# USB.net
KiCad netlist of a schematic drawn in Altium Designer
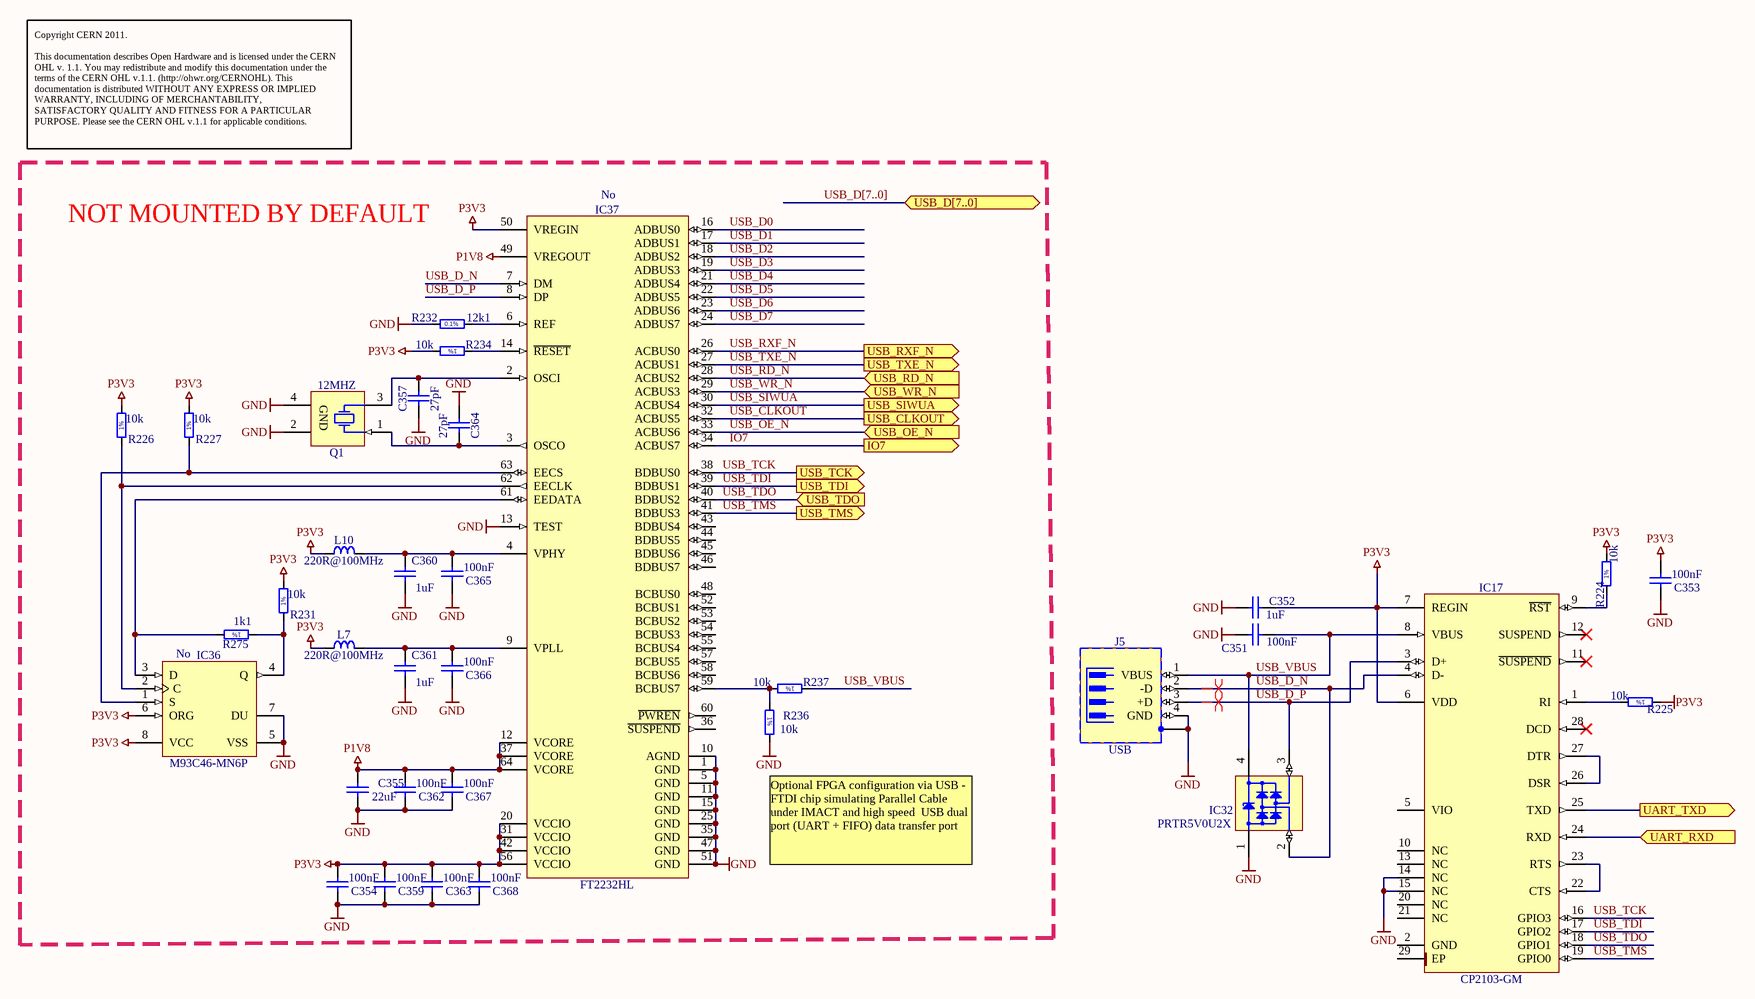
[diagram p0: USB.SchDoc]

(export (version "E")
  (design (tool "Eeschema 10.0.6"))
  (components
    (comp (ref "C351")
      (value "100nF")
      (footprint "CAPC1005X55N")
      (description "Non-polarised capacitor")
      (fields
        (field (name "PART NUMBER") "CC0402_100NF_16V_10%_X7R")
        (field (name "VOLTAGE") "16V")
        (field (name "AUTHOR") "CERN DEM JLC")
      )
      (libsource (lib "Capacitors") (part "Capacitor - non polarized"))
    )
    (comp (ref "C352")
      (value "1uF")
      (footprint "CAPC1608X87N")
      (description "Non-polarised capacitor")
      (fields
        (field (name "PART NUMBER") "CC0603_1UF_16V_10%_X7R")
        (field (name "VOLTAGE") "16V")
        (field (name "AUTHOR") "CERN DEM JLC")
      )
      (libsource (lib "Capacitors") (part "Capacitor - non polarized"))
    )
    (comp (ref "C353")
      (value "100nF")
      (footprint "CAPC1005X55N")
      (description "Non-polarised capacitor")
      (fields
        (field (name "PART NUMBER") "CC0402_100NF_16V_10%_X7R")
        (field (name "VOLTAGE") "16V")
        (field (name "AUTHOR") "CERN DEM JLC")
      )
      (libsource (lib "Capacitors") (part "Capacitor - non polarized"))
    )
    (comp (ref "C354")
      (value "100nF")
      (footprint "CAPC1005X55N")
      (description "Non-polarised capacitor")
      (fields
        (field (name "PART NUMBER") "CC0402_100NF_16V_10%_X7R")
        (field (name "VOLTAGE") "16V")
        (field (name "AUTHOR") "CERN DEM JLC")
      )
      (libsource (lib "Capacitors") (part "Capacitor - non polarized"))
    )
    (comp (ref "C355")
      (value "22uF")
      (footprint "CAPC3216X180N")
      (description "Non-polarised capacitor")
      (fields
        (field (name "PART NUMBER") "CC1206_22UF_10V_10%_X7R")
        (field (name "VOLTAGE") "10V")
        (field (name "AUTHOR") "CERN DEM JLC")
      )
      (libsource (lib "Capacitors") (part "Capacitor - non polarized"))
    )
    (comp (ref "C357")
      (value "27pF")
      (footprint "CAPC1608X87N")
      (description "Non-polarised capacitor")
      (fields
        (field (name "PART NUMBER") "CC0603_27PF_50V_5%_NP0")
        (field (name "VOLTAGE") "50V")
        (field (name "AUTHOR") "CERN DEM JLC")
      )
      (libsource (lib "Capacitors") (part "Capacitor - non polarized"))
    )
    (comp (ref "C359")
      (value "100nF")
      (footprint "CAPC1005X55N")
      (description "Non-polarised capacitor")
      (fields
        (field (name "PART NUMBER") "CC0402_100NF_16V_10%_X7R")
        (field (name "VOLTAGE") "16V")
        (field (name "AUTHOR") "CERN DEM JLC")
      )
      (libsource (lib "Capacitors") (part "Capacitor - non polarized"))
    )
    (comp (ref "C360")
      (value "1uF")
      (footprint "CAPC1608X87N")
      (description "Non-polarised capacitor")
      (fields
        (field (name "PART NUMBER") "CC0603_1UF_16V_10%_X7R")
        (field (name "VOLTAGE") "16V")
        (field (name "AUTHOR") "CERN DEM JLC")
      )
      (libsource (lib "Capacitors") (part "Capacitor - non polarized"))
    )
    (comp (ref "C361")
      (value "1uF")
      (footprint "CAPC1608X87N")
      (description "Non-polarised capacitor")
      (fields
        (field (name "PART NUMBER") "CC0603_1UF_16V_10%_X7R")
        (field (name "VOLTAGE") "16V")
        (field (name "AUTHOR") "CERN DEM JLC")
      )
      (libsource (lib "Capacitors") (part "Capacitor - non polarized"))
    )
    (comp (ref "C362")
      (value "100nF")
      (footprint "CAPC1005X55N")
      (description "Non-polarised capacitor")
      (fields
        (field (name "PART NUMBER") "CC0402_100NF_16V_10%_X7R")
        (field (name "VOLTAGE") "16V")
        (field (name "AUTHOR") "CERN DEM JLC")
      )
      (libsource (lib "Capacitors") (part "Capacitor - non polarized"))
    )
    (comp (ref "C363")
      (value "100nF")
      (footprint "CAPC1005X55N")
      (description "Non-polarised capacitor")
      (fields
        (field (name "PART NUMBER") "CC0402_100NF_16V_10%_X7R")
        (field (name "VOLTAGE") "16V")
        (field (name "AUTHOR") "CERN DEM JLC")
      )
      (libsource (lib "Capacitors") (part "Capacitor - non polarized"))
    )
    (comp (ref "C364")
      (value "27pF")
      (footprint "CAPC1608X87N")
      (description "Non-polarised capacitor")
      (fields
        (field (name "PART NUMBER") "CC0603_27PF_50V_5%_NP0")
        (field (name "VOLTAGE") "50V")
        (field (name "AUTHOR") "CERN DEM JLC")
      )
      (libsource (lib "Capacitors") (part "Capacitor - non polarized"))
    )
    (comp (ref "C365")
      (value "100nF")
      (footprint "CAPC1005X55N")
      (description "Non-polarised capacitor")
      (fields
        (field (name "PART NUMBER") "CC0402_100NF_16V_10%_X7R")
        (field (name "VOLTAGE") "16V")
        (field (name "AUTHOR") "CERN DEM JLC")
      )
      (libsource (lib "Capacitors") (part "Capacitor - non polarized"))
    )
    (comp (ref "C366")
      (value "100nF")
      (footprint "CAPC1005X55N")
      (description "Non-polarised capacitor")
      (fields
        (field (name "PART NUMBER") "CC0402_100NF_16V_10%_X7R")
        (field (name "VOLTAGE") "16V")
        (field (name "AUTHOR") "CERN DEM JLC")
      )
      (libsource (lib "Capacitors") (part "Capacitor - non polarized"))
    )
    (comp (ref "C367")
      (value "100nF")
      (footprint "CAPC1005X55N")
      (description "Non-polarised capacitor")
      (fields
        (field (name "PART NUMBER") "CC0402_100NF_16V_10%_X7R")
        (field (name "VOLTAGE") "16V")
        (field (name "AUTHOR") "CERN DEM JLC")
      )
      (libsource (lib "Capacitors") (part "Capacitor - non polarized"))
    )
    (comp (ref "C368")
      (value "100nF")
      (footprint "CAPC1005X55N")
      (description "Non-polarised capacitor")
      (fields
        (field (name "PART NUMBER") "CC0402_100NF_16V_10%_X7R")
        (field (name "VOLTAGE") "16V")
        (field (name "AUTHOR") "CERN DEM JLC")
      )
      (libsource (lib "Capacitors") (part "Capacitor - non polarized"))
    )
    (comp (ref "IC17")
      (value "CP2103-GM")
      (footprint "QFN50P500X500X100-29N-S335")
      (description "Single-Chip USB to UART Bridge")
      (fields (field (name "MANUFACTURER") "SILICON LABS") (field (name "AUTHOR") "CERN DEM JLC"))
      (libsource (lib "ICs And Semiconductors") (part "CP2103-GM"))
    )
    (comp (ref "IC32")
      (value "PRTR5V0U2X")
      (footprint "SOT190P230X110-4N")
      (description "Ultra Low Capacitance Double Rail-to-Rail ESD Protection Diode")
      (fields
        (field (name "VOLTAGE") "5.5V")
        (field (name "MANUFACTURER") "PHILIPS NXP")
        (field (name "AUTHOR") "CERN DEM JLC")
      )
      (libsource (lib "ICs And Semiconductors") (part "PRTR5V0U2X"))
    )
    (comp (ref "IC36")
      (value "M93C46-MN6P")
      (footprint "SOIC127P600X175-8N")
      (description "1Kb (x8/x16) Serial Microwire Bus EEPROM")
      (fields
        (field (name "MANUFACTURER") "ST MICROELECTRONICS")
        (field (name "MOUNTED") "No")
        (field (name "AUTHOR") "CERN DEM JLC")
      )
      (libsource (lib "ICs And Semiconductors") (part "M93C46-MN"))
    )
    (comp (ref "IC37")
      (value "FT2232HL")
      (footprint "QFP50P1200X1200X160-64N")
      (description "Dual High Speed USB to Multipurpose UART/FIFO IC")
      (fields
        (field (name "MANUFACTURER") "FUTURE TECHNOLOGY DEVICES INTERNATIONAL (FTDI)")
        (field (name "MOUNTED") "No")
        (field (name "AUTHOR") "CERN DEM JLC")
      )
      (libsource (lib "ICs And Semiconductors") (part "FT2232H"))
    )
    (comp (ref "J5")
      (value "USB")
      (footprint "TYCO_292304-1")
      (description "4 Pin + 1 Shield USB Receptacle")
      (fields
        (field (name "PART NUMBER") "TYCO_292304-1")
        (field (name "MANUFACTURER") "TYCO ELECTRONICS")
        (field (name "AUTHOR") "CERN DEM JLC")
      )
      (libsource (lib "Connectors") (part "Connector USB 4 Pin + 1Shield"))
    )
    (comp (ref "L7")
      (value "220R@100MHz")
      (footprint "INDC2012X105N")
      (description "Inductor")
      (fields
        (field (name "PART NUMBER") "IND0805_MURATA_BLM21PG221SN1D")
        (field (name "POWER") "2A")
        (field (name "AUTHOR") "CERN DEM JLC")
      )
      (libsource (lib "Inductors & Transformers") (part "Inductor"))
    )
    (comp (ref "L10")
      (value "220R@100MHz")
      (footprint "INDC2012X105N")
      (description "Inductor")
      (fields
        (field (name "PART NUMBER") "IND0805_MURATA_BLM21PG221SN1D")
        (field (name "POWER") "2A")
        (field (name "AUTHOR") "CERN DEM JLC")
      )
      (libsource (lib "Inductors & Transformers") (part "Inductor"))
    )
    (comp (ref "Q1")
      (value "12MHZ")
      (footprint "XTAL_ABRACON_ABM3B")
      (description "Crystal 4 pins 1=XTAL Control 2=GND3=XTAL 4=GND")
      (fields
        (field (name "PART NUMBER") "XTAL_12MHZ_ABRACON_ABM3B-12.000MHZ-B2-T")
        (field (name "MANUFACTURER") "ABRACON")
        (field (name "AUTHOR") "CERN DEM JLC")
      )
      (libsource (lib "ICs And Semiconductors") (part "Quartz Crystal 1X 2GND 3X 4GND"))
    )
    (comp (ref "R224")
      (value "10k")
      (footprint "RESC1608X55N")
      (description "Resistor - 1%")
      (fields
        (field (name "PART NUMBER") "R0603_10K_1%_0.1W_100PPM")
        (field (name "POWER") "0.1W")
        (field (name "AUTHOR") "CERN DEM JLC")
      )
      (libsource (lib "Resistors") (part "Resistor - 1%"))
    )
    (comp (ref "R225")
      (value "10k")
      (footprint "RESC1608X55N")
      (description "Resistor - 1%")
      (fields
        (field (name "PART NUMBER") "R0603_10K_1%_0.1W_100PPM")
        (field (name "POWER") "0.1W")
        (field (name "AUTHOR") "CERN DEM JLC")
      )
      (libsource (lib "Resistors") (part "Resistor - 1%"))
    )
    (comp (ref "R226")
      (value "10k")
      (footprint "RESC1608X55N")
      (description "Resistor - 1%")
      (fields
        (field (name "PART NUMBER") "R0603_10K_1%_0.1W_100PPM")
        (field (name "POWER") "0.1W")
        (field (name "AUTHOR") "CERN DEM JLC")
      )
      (libsource (lib "Resistors") (part "Resistor - 1%"))
    )
    (comp (ref "R227")
      (value "10k")
      (footprint "RESC1608X55N")
      (description "Resistor - 1%")
      (fields
        (field (name "PART NUMBER") "R0603_10K_1%_0.1W_100PPM")
        (field (name "POWER") "0.1W")
        (field (name "AUTHOR") "CERN DEM JLC")
      )
      (libsource (lib "Resistors") (part "Resistor - 1%"))
    )
    (comp (ref "R231")
      (value "10k")
      (footprint "RESC1608X55N")
      (description "Resistor - 1%")
      (fields
        (field (name "PART NUMBER") "R0603_10K_1%_0.1W_100PPM")
        (field (name "POWER") "0.1W")
        (field (name "AUTHOR") "CERN DEM JLC")
      )
      (libsource (lib "Resistors") (part "Resistor - 1%"))
    )
    (comp (ref "R232")
      (value "12k1")
      (footprint "RESC1608X55N")
      (description "Resistor - 0.1%")
      (fields
        (field (name "PART NUMBER") "R0603_12K1_0.1%_0.063W_10PPM")
        (field (name "POWER") "0.063W")
        (field (name "AUTHOR") "CERN DEM JLC")
      )
      (libsource (lib "Resistors") (part "Resistor - 0.1%"))
    )
    (comp (ref "R234")
      (value "10k")
      (footprint "RESC1608X55N")
      (description "Resistor - 1%")
      (fields
        (field (name "PART NUMBER") "R0603_10K_1%_0.1W_100PPM")
        (field (name "POWER") "0.1W")
        (field (name "AUTHOR") "CERN DEM JLC")
      )
      (libsource (lib "Resistors") (part "Resistor - 1%"))
    )
    (comp (ref "R236")
      (value "10k")
      (footprint "RESC1608X55N")
      (description "Resistor - 1%")
      (fields
        (field (name "PART NUMBER") "R0603_10K_1%_0.1W_100PPM")
        (field (name "POWER") "0.1W")
        (field (name "AUTHOR") "CERN DEM JLC")
      )
      (libsource (lib "Resistors") (part "Resistor - 1%"))
    )
    (comp (ref "R237")
      (value "10k")
      (footprint "RESC1608X55N")
      (description "Resistor - 1%")
      (fields
        (field (name "PART NUMBER") "R0603_10K_1%_0.1W_100PPM")
        (field (name "POWER") "0.1W")
        (field (name "AUTHOR") "CERN DEM JLC")
      )
      (libsource (lib "Resistors") (part "Resistor - 1%"))
    )
    (comp (ref "R275")
      (value "1k1")
      (footprint "RESC1608X55N")
      (description "Resistor - 1%")
      (fields
        (field (name "PART NUMBER") "R0603_1K1_1%_0.1W_100PPM")
        (field (name "POWER") "0.1W")
        (field (name "AUTHOR") "CERN DEM JLC")
      )
      (libsource (lib "Resistors") (part "Resistor - 1%"))
    )
  )
  (nets
    (net (code "1") (name "/IO7") (class "Default")
      (node (ref "IC37") (pin "34") (pinfunction "ACBUS7_34") (pintype "bidirectional"))
    )
    (net (code "2") (name "/UART_RXD") (class "Default")
      (node (ref "IC17") (pin "24") (pinfunction "RXD_24") (pintype "input"))
    )
    (net (code "3") (name "/UART_TXD") (class "Default")
      (node (ref "IC17") (pin "25") (pinfunction "TXD_25") (pintype "output"))
    )
    (net (code "4") (name "/USB_CLKOUT") (class "Default")
      (node (ref "IC37") (pin "32") (pinfunction "ACBUS5_32") (pintype "bidirectional"))
    )
    (net (code "5") (name "/USB_D0") (class "Default")
      (node (ref "IC37") (pin "16") (pinfunction "ADBUS0_16") (pintype "bidirectional"))
    )
    (net (code "6") (name "/USB_D1") (class "Default")
      (node (ref "IC37") (pin "17") (pinfunction "ADBUS1_17") (pintype "bidirectional"))
    )
    (net (code "7") (name "/USB_D2") (class "Default")
      (node (ref "IC37") (pin "18") (pinfunction "ADBUS2_18") (pintype "bidirectional"))
    )
    (net (code "8") (name "/USB_D3") (class "Default")
      (node (ref "IC37") (pin "19") (pinfunction "ADBUS3_19") (pintype "bidirectional"))
    )
    (net (code "9") (name "/USB_D4") (class "Default")
      (node (ref "IC37") (pin "21") (pinfunction "ADBUS4_21") (pintype "bidirectional"))
    )
    (net (code "10") (name "/USB_D5") (class "Default")
      (node (ref "IC37") (pin "22") (pinfunction "ADBUS5_22") (pintype "bidirectional"))
    )
    (net (code "11") (name "/USB_D6") (class "Default")
      (node (ref "IC37") (pin "23") (pinfunction "ADBUS6_23") (pintype "bidirectional"))
    )
    (net (code "12") (name "/USB_D7") (class "Default")
      (node (ref "IC37") (pin "24") (pinfunction "ADBUS7_24") (pintype "bidirectional"))
    )
    (net (code "14") (name "/USB_D_N") (class "Default")
      (node (ref "IC17") (pin "4") (pinfunction "D-_4") (pintype "bidirectional"))
      (node (ref "IC32") (pin "2") (pinfunction "I/O1_2") (pintype "bidirectional"))
      (node (ref "IC37") (pin "7") (pinfunction "DM_7") (pintype "input"))
      (node (ref "J5") (pin "2") (pinfunction "-D_2") (pintype "bidirectional"))
    )
    (net (code "15") (name "/USB_D_P") (class "Default")
      (node (ref "IC17") (pin "3") (pinfunction "D+_3") (pintype "bidirectional"))
      (node (ref "IC32") (pin "3") (pinfunction "I/O2_3") (pintype "bidirectional"))
      (node (ref "IC37") (pin "8") (pinfunction "DP_8") (pintype "input"))
      (node (ref "J5") (pin "3") (pinfunction "+D_3") (pintype "bidirectional"))
    )
    (net (code "16") (name "/USB_OE_N") (class "Default")
      (node (ref "IC37") (pin "33") (pinfunction "ACBUS6_33") (pintype "bidirectional"))
    )
    (net (code "17") (name "/USB_RD_N") (class "Default")
      (node (ref "IC37") (pin "28") (pinfunction "ACBUS2_28") (pintype "bidirectional"))
    )
    (net (code "18") (name "/USB_RXF_N") (class "Default")
      (node (ref "IC37") (pin "26") (pinfunction "ACBUS0_26") (pintype "bidirectional"))
    )
    (net (code "19") (name "/USB_SIWUA") (class "Default")
      (node (ref "IC37") (pin "30") (pinfunction "ACBUS4_30") (pintype "bidirectional"))
    )
    (net (code "20") (name "/USB_TCK") (class "Default")
      (node (ref "IC17") (pin "16") (pinfunction "GPIO3_16") (pintype "bidirectional"))
      (node (ref "IC37") (pin "38") (pinfunction "BDBUS0_38") (pintype "bidirectional"))
    )
    (net (code "21") (name "/USB_TDI") (class "Default")
      (node (ref "IC17") (pin "17") (pinfunction "GPIO2_17") (pintype "bidirectional"))
      (node (ref "IC37") (pin "39") (pinfunction "BDBUS1_39") (pintype "bidirectional"))
    )
    (net (code "22") (name "/USB_TDO") (class "Default")
      (node (ref "IC17") (pin "18") (pinfunction "GPIO1_18") (pintype "bidirectional"))
      (node (ref "IC37") (pin "40") (pinfunction "BDBUS2_40") (pintype "bidirectional"))
    )
    (net (code "23") (name "/USB_TMS") (class "Default")
      (node (ref "IC17") (pin "19") (pinfunction "GPIO0_19") (pintype "bidirectional"))
      (node (ref "IC37") (pin "41") (pinfunction "BDBUS3_41") (pintype "bidirectional"))
    )
    (net (code "24") (name "/USB_TXE_N") (class "Default")
      (node (ref "IC37") (pin "27") (pinfunction "ACBUS1_27") (pintype "bidirectional"))
    )
    (net (code "25") (name "/USB_VBUS") (class "Default")
      (node (ref "C351") (pin "1") (pinfunction "1_1") (pintype "passive"))
      (node (ref "IC17") (pin "8") (pinfunction "VBUS_8") (pintype "input"))
      (node (ref "IC32") (pin "4") (pinfunction "VCC_4") (pintype "power_in"))
      (node (ref "J5") (pin "1") (pinfunction "VBUS_1") (pintype "bidirectional"))
      (node (ref "R237") (pin "1") (pinfunction "1_1") (pintype "passive"))
    )
    (net (code "26") (name "/USB_WR_N") (class "Default")
      (node (ref "IC37") (pin "29") (pinfunction "ACBUS3_29") (pintype "bidirectional"))
    )
    (net (code "27") (name "GND") (class "Default")
      (node (ref "C351") (pin "2") (pinfunction "2_2") (pintype "passive"))
      (node (ref "C352") (pin "2") (pinfunction "2_2") (pintype "passive"))
      (node (ref "C353") (pin "2") (pinfunction "2_2") (pintype "passive"))
      (node (ref "C354") (pin "2") (pinfunction "2_2") (pintype "passive"))
      (node (ref "C355") (pin "1") (pinfunction "1_1") (pintype "passive"))
      (node (ref "C357") (pin "1") (pinfunction "1_1") (pintype "passive"))
      (node (ref "C359") (pin "2") (pinfunction "2_2") (pintype "passive"))
      (node (ref "C360") (pin "1") (pinfunction "1_1") (pintype "passive"))
      (node (ref "C361") (pin "1") (pinfunction "1_1") (pintype "passive"))
      (node (ref "C362") (pin "2") (pinfunction "2_2") (pintype "passive"))
      (node (ref "C363") (pin "2") (pinfunction "2_2") (pintype "passive"))
      (node (ref "C364") (pin "1") (pinfunction "1_1") (pintype "passive"))
      (node (ref "C365") (pin "2") (pinfunction "2_2") (pintype "passive"))
      (node (ref "C366") (pin "2") (pinfunction "2_2") (pintype "passive"))
      (node (ref "C367") (pin "2") (pinfunction "2_2") (pintype "passive"))
      (node (ref "C368") (pin "2") (pinfunction "2_2") (pintype "passive"))
      (node (ref "IC17") (pin "14") (pinfunction "NC_14") (pintype "passive"))
      (node (ref "IC17") (pin "15") (pinfunction "NC_15") (pintype "passive"))
      (node (ref "IC32") (pin "1") (pinfunction "GND_1") (pintype "power_in"))
      (node (ref "IC36") (pin "5") (pinfunction "VSS_5") (pintype "power_in"))
      (node (ref "IC36") (pin "7") (pinfunction "DU_7") (pintype "passive"))
      (node (ref "IC37") (pin "1") (pinfunction "GND_1") (pintype "power_in"))
      (node (ref "IC37") (pin "10") (pinfunction "AGND_10") (pintype "power_in"))
      (node (ref "IC37") (pin "11") (pinfunction "GND_11") (pintype "power_in"))
      (node (ref "IC37") (pin "13") (pinfunction "TEST_13") (pintype "input"))
      (node (ref "IC37") (pin "15") (pinfunction "GND_15") (pintype "power_in"))
      (node (ref "IC37") (pin "25") (pinfunction "GND_25") (pintype "power_in"))
      (node (ref "IC37") (pin "35") (pinfunction "GND_35") (pintype "power_in"))
      (node (ref "IC37") (pin "47") (pinfunction "GND_47") (pintype "power_in"))
      (node (ref "IC37") (pin "5") (pinfunction "GND_5") (pintype "power_in"))
      (node (ref "IC37") (pin "51") (pinfunction "GND_51") (pintype "power_in"))
      (node (ref "J5") (pin "4") (pinfunction "GND_4") (pintype "bidirectional"))
      (node (ref "J5") (pin "5") (pinfunction "SH_5") (pintype "power_in"))
      (node (ref "Q1") (pin "2") (pinfunction "GND_2") (pintype "power_in"))
      (node (ref "Q1") (pin "4") (pinfunction "GND_4") (pintype "power_in"))
      (node (ref "R232") (pin "1") (pinfunction "1_1") (pintype "passive"))
      (node (ref "R236") (pin "2") (pinfunction "2_2") (pintype "passive"))
    )
    (net (code "28") (name "Net-(IC17-CTS)") (class "Default")
      (node (ref "IC17") (pin "22") (pinfunction "CTS_22") (pintype "input"))
      (node (ref "IC17") (pin "23") (pinfunction "RTS_23") (pintype "output"))
    )
    (net (code "29") (name "Net-(IC17-DSR)") (class "Default")
      (node (ref "IC17") (pin "26") (pinfunction "DSR_26") (pintype "input"))
      (node (ref "IC17") (pin "27") (pinfunction "DTR_27") (pintype "output"))
    )
    (net (code "30") (name "Net-(IC17-RI)") (class "Default")
      (node (ref "IC17") (pin "1") (pinfunction "RI_1") (pintype "input"))
      (node (ref "R225") (pin "2") (pinfunction "2_2") (pintype "passive"))
    )
    (net (code "31") (name "Net-(IC17-~{RST})") (class "Default")
      (node (ref "IC17") (pin "9") (pinfunction "~{RST}_9") (pintype "bidirectional"))
      (node (ref "R224") (pin "1") (pinfunction "1_1") (pintype "passive"))
    )
    (net (code "32") (name "Net-(IC36-C)") (class "Default")
      (node (ref "IC36") (pin "2") (pinfunction "C_2") (pintype "input"))
      (node (ref "IC37") (pin "62") (pinfunction "EECLK_62") (pintype "output"))
      (node (ref "R226") (pin "1") (pinfunction "1_1") (pintype "passive"))
    )
    (net (code "33") (name "Net-(IC36-D)") (class "Default")
      (node (ref "IC36") (pin "3") (pinfunction "D_3") (pintype "input"))
      (node (ref "IC37") (pin "61") (pinfunction "EEDATA_61") (pintype "bidirectional"))
      (node (ref "R275") (pin "2") (pinfunction "2_2") (pintype "passive"))
    )
    (net (code "34") (name "Net-(IC36-Q)") (class "Default")
      (node (ref "IC36") (pin "4") (pinfunction "Q_4") (pintype "output"))
      (node (ref "R231") (pin "1") (pinfunction "1_1") (pintype "passive"))
      (node (ref "R275") (pin "1") (pinfunction "1_1") (pintype "passive"))
    )
    (net (code "35") (name "Net-(IC36-S)") (class "Default")
      (node (ref "IC36") (pin "1") (pinfunction "S_1") (pintype "input"))
      (node (ref "IC37") (pin "63") (pinfunction "EECS_63") (pintype "bidirectional"))
      (node (ref "R227") (pin "1") (pinfunction "1_1") (pintype "passive"))
    )
    (net (code "36") (name "Net-(IC37-BCBUS7)") (class "Default")
      (node (ref "IC37") (pin "59") (pinfunction "BCBUS7_59") (pintype "bidirectional"))
      (node (ref "R236") (pin "1") (pinfunction "1_1") (pintype "passive"))
      (node (ref "R237") (pin "2") (pinfunction "2_2") (pintype "passive"))
    )
    (net (code "37") (name "Net-(IC37-OSCI)") (class "Default")
      (node (ref "C357") (pin "2") (pinfunction "2_2") (pintype "passive"))
      (node (ref "IC37") (pin "2") (pinfunction "OSCI_2") (pintype "input"))
      (node (ref "Q1") (pin "3") (pinfunction "X_3") (pintype "power_in"))
    )
    (net (code "38") (name "Net-(IC37-OSCO)") (class "Default")
      (node (ref "C364") (pin "2") (pinfunction "2_2") (pintype "passive"))
      (node (ref "IC37") (pin "3") (pinfunction "OSCO_3") (pintype "output"))
      (node (ref "Q1") (pin "1") (pinfunction "X_1") (pintype "input"))
    )
    (net (code "39") (name "Net-(IC37-REF)") (class "Default")
      (node (ref "IC37") (pin "6") (pinfunction "REF_6") (pintype "input"))
      (node (ref "R232") (pin "2") (pinfunction "2_2") (pintype "passive"))
    )
    (net (code "40") (name "Net-(IC37-VPHY)") (class "Default")
      (node (ref "C360") (pin "2") (pinfunction "2_2") (pintype "passive"))
      (node (ref "C365") (pin "1") (pinfunction "1_1") (pintype "passive"))
      (node (ref "IC37") (pin "4") (pinfunction "VPHY_4") (pintype "power_in"))
      (node (ref "L10") (pin "2") (pinfunction "2_2") (pintype "passive"))
    )
    (net (code "41") (name "Net-(IC37-VPLL)") (class "Default")
      (node (ref "C361") (pin "2") (pinfunction "2_2") (pintype "passive"))
      (node (ref "C366") (pin "1") (pinfunction "1_1") (pintype "passive"))
      (node (ref "IC37") (pin "9") (pinfunction "VPLL_9") (pintype "power_in"))
      (node (ref "L7") (pin "2") (pinfunction "2_2") (pintype "passive"))
    )
    (net (code "42") (name "Net-(IC37-~{RESET})") (class "Default")
      (node (ref "IC37") (pin "14") (pinfunction "~{RESET}_14") (pintype "input"))
      (node (ref "R234") (pin "1") (pinfunction "1_1") (pintype "passive"))
    )
    (net (code "43") (name "P1V8") (class "Default")
      (node (ref "C355") (pin "2") (pinfunction "2_2") (pintype "passive"))
      (node (ref "C362") (pin "1") (pinfunction "1_1") (pintype "passive"))
      (node (ref "C367") (pin "1") (pinfunction "1_1") (pintype "passive"))
      (node (ref "IC37") (pin "12") (pinfunction "VCORE_12") (pintype "power_in"))
      (node (ref "IC37") (pin "37") (pinfunction "VCORE_37") (pintype "power_in"))
      (node (ref "IC37") (pin "49") (pinfunction "VREGOUT_49") (pintype "power_in"))
      (node (ref "IC37") (pin "64") (pinfunction "VCORE_64") (pintype "power_in"))
    )
    (net (code "44") (name "P3V3") (class "Default")
      (node (ref "C352") (pin "1") (pinfunction "1_1") (pintype "passive"))
      (node (ref "C353") (pin "1") (pinfunction "1_1") (pintype "passive"))
      (node (ref "C354") (pin "1") (pinfunction "1_1") (pintype "passive"))
      (node (ref "C359") (pin "1") (pinfunction "1_1") (pintype "passive"))
      (node (ref "C363") (pin "1") (pinfunction "1_1") (pintype "passive"))
      (node (ref "C368") (pin "1") (pinfunction "1_1") (pintype "passive"))
      (node (ref "IC17") (pin "6") (pinfunction "VDD_6") (pintype "power_in"))
      (node (ref "IC17") (pin "7") (pinfunction "REGIN_7") (pintype "power_in"))
      (node (ref "IC36") (pin "6") (pinfunction "ORG_6") (pintype "input"))
      (node (ref "IC36") (pin "8") (pinfunction "VCC_8") (pintype "power_in"))
      (node (ref "IC37") (pin "20") (pinfunction "VCCIO_20") (pintype "power_in"))
      (node (ref "IC37") (pin "31") (pinfunction "VCCIO_31") (pintype "power_in"))
      (node (ref "IC37") (pin "42") (pinfunction "VCCIO_42") (pintype "power_in"))
      (node (ref "IC37") (pin "50") (pinfunction "VREGIN_50") (pintype "power_in"))
      (node (ref "IC37") (pin "56") (pinfunction "VCCIO_56") (pintype "power_in"))
      (node (ref "L10") (pin "1") (pinfunction "1_1") (pintype "passive"))
      (node (ref "L7") (pin "1") (pinfunction "1_1") (pintype "passive"))
      (node (ref "R224") (pin "2") (pinfunction "2_2") (pintype "passive"))
      (node (ref "R225") (pin "1") (pinfunction "1_1") (pintype "passive"))
      (node (ref "R226") (pin "2") (pinfunction "2_2") (pintype "passive"))
      (node (ref "R227") (pin "2") (pinfunction "2_2") (pintype "passive"))
      (node (ref "R231") (pin "2") (pinfunction "2_2") (pintype "passive"))
      (node (ref "R234") (pin "2") (pinfunction "2_2") (pintype "passive"))
    )
    (net (code "45") (name "unconnected-(IC17-DCD-Pad28)") (class "Default")
      (node (ref "IC17") (pin "28") (pinfunction "DCD_28") (pintype "input+no_connect"))
    )
    (net (code "46") (name "unconnected-(IC17-EP-Pad29)") (class "Default")
      (node (ref "IC17") (pin "29") (pinfunction "EP_29") (pintype "power_in"))
    )
    (net (code "47") (name "unconnected-(IC17-GND-Pad2)") (class "Default")
      (node (ref "IC17") (pin "2") (pinfunction "GND_2") (pintype "power_in"))
    )
    (net (code "48") (name "unconnected-(IC17-NC-Pad10)") (class "Default")
      (node (ref "IC17") (pin "10") (pinfunction "NC_10") (pintype "passive"))
    )
    (net (code "49") (name "unconnected-(IC17-NC-Pad13)") (class "Default")
      (node (ref "IC17") (pin "13") (pinfunction "NC_13") (pintype "passive"))
    )
    (net (code "50") (name "unconnected-(IC17-NC-Pad20)") (class "Default")
      (node (ref "IC17") (pin "20") (pinfunction "NC_20") (pintype "passive"))
    )
    (net (code "51") (name "unconnected-(IC17-NC-Pad21)") (class "Default")
      (node (ref "IC17") (pin "21") (pinfunction "NC_21") (pintype "passive"))
    )
    (net (code "52") (name "unconnected-(IC17-SUSPEND-Pad12)") (class "Default")
      (node (ref "IC17") (pin "12") (pinfunction "SUSPEND_12") (pintype "output+no_connect"))
    )
    (net (code "53") (name "unconnected-(IC17-VIO-Pad5)") (class "Default")
      (node (ref "IC17") (pin "5") (pinfunction "VIO_5") (pintype "power_in"))
    )
    (net (code "54") (name "unconnected-(IC17-~{SUSPEND}-Pad11)") (class "Default")
      (node (ref "IC17") (pin "11") (pinfunction "~{SUSPEND}_11") (pintype "output+no_connect"))
    )
    (net (code "55") (name "unconnected-(IC37-BCBUS0-Pad48)") (class "Default")
      (node (ref "IC37") (pin "48") (pinfunction "BCBUS0_48") (pintype "bidirectional"))
    )
    (net (code "56") (name "unconnected-(IC37-BCBUS1-Pad52)") (class "Default")
      (node (ref "IC37") (pin "52") (pinfunction "BCBUS1_52") (pintype "bidirectional"))
    )
    (net (code "57") (name "unconnected-(IC37-BCBUS2-Pad53)") (class "Default")
      (node (ref "IC37") (pin "53") (pinfunction "BCBUS2_53") (pintype "bidirectional"))
    )
    (net (code "58") (name "unconnected-(IC37-BCBUS3-Pad54)") (class "Default")
      (node (ref "IC37") (pin "54") (pinfunction "BCBUS3_54") (pintype "bidirectional"))
    )
    (net (code "59") (name "unconnected-(IC37-BCBUS4-Pad55)") (class "Default")
      (node (ref "IC37") (pin "55") (pinfunction "BCBUS4_55") (pintype "bidirectional"))
    )
    (net (code "60") (name "unconnected-(IC37-BCBUS5-Pad57)") (class "Default")
      (node (ref "IC37") (pin "57") (pinfunction "BCBUS5_57") (pintype "bidirectional"))
    )
    (net (code "61") (name "unconnected-(IC37-BCBUS6-Pad58)") (class "Default")
      (node (ref "IC37") (pin "58") (pinfunction "BCBUS6_58") (pintype "bidirectional"))
    )
    (net (code "62") (name "unconnected-(IC37-BDBUS4-Pad43)") (class "Default")
      (node (ref "IC37") (pin "43") (pinfunction "BDBUS4_43") (pintype "bidirectional"))
    )
    (net (code "63") (name "unconnected-(IC37-BDBUS5-Pad44)") (class "Default")
      (node (ref "IC37") (pin "44") (pinfunction "BDBUS5_44") (pintype "bidirectional"))
    )
    (net (code "64") (name "unconnected-(IC37-BDBUS6-Pad45)") (class "Default")
      (node (ref "IC37") (pin "45") (pinfunction "BDBUS6_45") (pintype "bidirectional"))
    )
    (net (code "65") (name "unconnected-(IC37-BDBUS7-Pad46)") (class "Default")
      (node (ref "IC37") (pin "46") (pinfunction "BDBUS7_46") (pintype "bidirectional"))
    )
    (net (code "66") (name "unconnected-(IC37-~{PWREN}-Pad60)") (class "Default")
      (node (ref "IC37") (pin "60") (pinfunction "~{PWREN}_60") (pintype "output"))
    )
    (net (code "67") (name "unconnected-(IC37-~{SUSPEND}-Pad36)") (class "Default")
      (node (ref "IC37") (pin "36") (pinfunction "~{SUSPEND}_36") (pintype "output"))
    )
  )
)
